# USB_ETH_Sch.net
KiCad netlist of a schematic drawn in Altium Designer
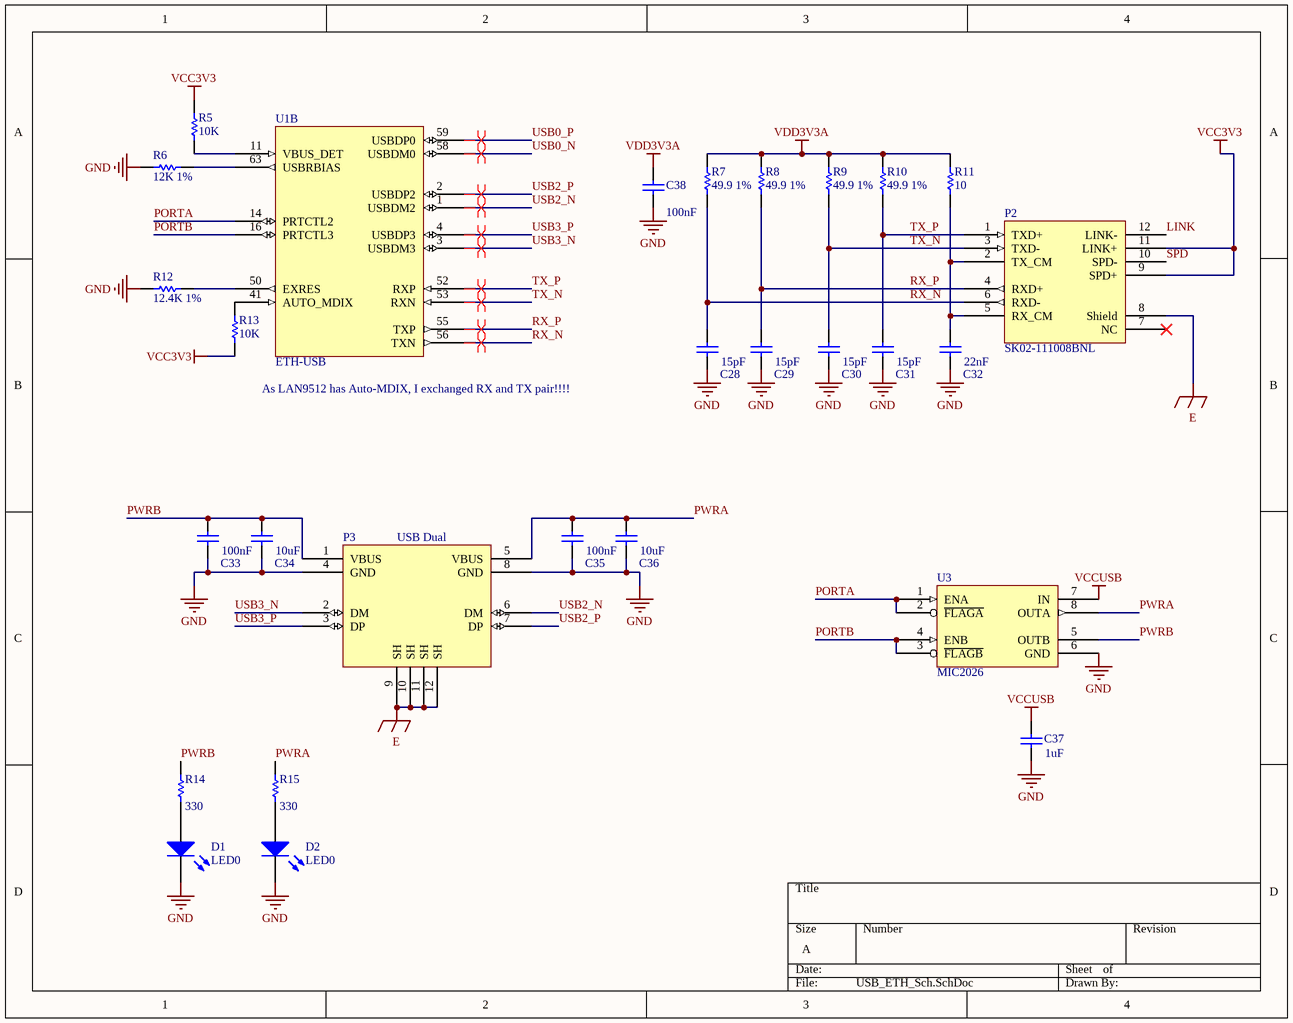
[diagram p0: USB_ETH_Sch.SchDoc]

(export (version "E")
  (design (tool "Eeschema 10.0.6"))
  (components
    (comp (ref "C28")
      (value "15pF")
      (footprint "C0805")
      (description "Capacitor")
      (fields (field (name "Comment") "Cap") (field (name "PUBLISHER") "Altium Limited"))
      (libsource (lib "Miscellaneous Devices") (part "Cap"))
    )
    (comp (ref "C29")
      (value "15pF")
      (footprint "C0805")
      (description "Capacitor")
      (fields (field (name "Comment") "Cap") (field (name "PUBLISHER") "Altium Limited"))
      (libsource (lib "Miscellaneous Devices") (part "Cap"))
    )
    (comp (ref "C30")
      (value "15pF")
      (footprint "C0805")
      (description "Capacitor")
      (fields (field (name "Comment") "Cap") (field (name "PUBLISHER") "Altium Limited"))
      (libsource (lib "Miscellaneous Devices") (part "Cap"))
    )
    (comp (ref "C31")
      (value "15pF")
      (footprint "C0805")
      (description "Capacitor")
      (fields (field (name "Comment") "Cap") (field (name "PUBLISHER") "Altium Limited"))
      (libsource (lib "Miscellaneous Devices") (part "Cap"))
    )
    (comp (ref "C32")
      (value "22nF")
      (footprint "C0805")
      (description "Capacitor")
      (fields (field (name "Comment") "Cap") (field (name "PUBLISHER") "Altium Limited"))
      (libsource (lib "Miscellaneous Devices") (part "Cap"))
    )
    (comp (ref "C33")
      (value "100nF")
      (footprint "C0805")
      (description "Capacitor")
      (fields (field (name "Comment") "Cap") (field (name "PUBLISHER") "Altium Limited"))
      (libsource (lib "Miscellaneous Devices") (part "Cap"))
    )
    (comp (ref "C34")
      (value "10uF")
      (footprint "C0805")
      (description "Capacitor")
      (fields (field (name "Comment") "Cap") (field (name "PUBLISHER") "Altium Limited"))
      (libsource (lib "Miscellaneous Devices") (part "Cap"))
    )
    (comp (ref "C35")
      (value "100nF")
      (footprint "C0805")
      (description "Capacitor")
      (fields (field (name "Comment") "Cap") (field (name "PUBLISHER") "Altium Limited"))
      (libsource (lib "Miscellaneous Devices") (part "Cap"))
    )
    (comp (ref "C36")
      (value "10uF")
      (footprint "C0805")
      (description "Capacitor")
      (fields (field (name "Comment") "Cap") (field (name "PUBLISHER") "Altium Limited"))
      (libsource (lib "Miscellaneous Devices") (part "Cap"))
    )
    (comp (ref "C37")
      (value "1uF")
      (footprint "C0805")
      (description "Capacitor")
      (fields (field (name "Comment") "Cap") (field (name "PUBLISHER") "Altium Limited"))
      (libsource (lib "Miscellaneous Devices") (part "Cap"))
    )
    (comp (ref "C38")
      (value "100nF")
      (footprint "C0805")
      (description "Capacitor")
      (fields (field (name "Comment") "Cap") (field (name "PUBLISHER") "Altium Limited"))
      (libsource (lib "Miscellaneous Devices") (part "Cap"))
    )
    (comp (ref "D1")
      (value "LED0")
      (footprint "SMD_LED_1206")
      (description "Typical INFRARED GaAs LED")
      (fields (field (name "PUBLISHER") "Altium Limited"))
      (libsource (lib "Miscellaneous Devices") (part "LED0"))
    )
    (comp (ref "D2")
      (value "LED0")
      (footprint "SMD_LED_1206")
      (description "Typical INFRARED GaAs LED")
      (fields (field (name "PUBLISHER") "Altium Limited"))
      (libsource (lib "Miscellaneous Devices") (part "LED0"))
    )
    (comp (ref "P2")
      (value "SK02-111008BNL")
      (footprint "RJ45+MAG")
      (description "Ethernet")
      (libsource (lib "Conn_Schlib") (part "SK02-111008BNL"))
    )
    (comp (ref "P3")
      (value "USB Dual")
      (footprint "USB_Duble")
      (libsource (lib "Connector_IntLib") (part "USB_Double_Female"))
    )
    (comp (ref "R5")
      (value "10K")
      (footprint "c0805")
      (description "Resistor")
      (fields (field (name "Comment") "Res1") (field (name "PUBLISHER") "Altium Limited"))
      (libsource (lib "Miscellaneous Devices") (part "Res1"))
    )
    (comp (ref "R6")
      (value "12K 1%")
      (footprint "c0805")
      (description "Resistor")
      (fields (field (name "Comment") "Res1") (field (name "PUBLISHER") "Altium Limited"))
      (libsource (lib "Miscellaneous Devices") (part "Res1"))
    )
    (comp (ref "R7")
      (value "49.9 1%")
      (footprint "c0805")
      (description "Resistor")
      (fields (field (name "Comment") "Res1") (field (name "PUBLISHER") "Altium Limited"))
      (libsource (lib "Miscellaneous Devices") (part "Res1"))
    )
    (comp (ref "R8")
      (value "49.9 1%")
      (footprint "c0805")
      (description "Resistor")
      (fields (field (name "Comment") "Res1") (field (name "PUBLISHER") "Altium Limited"))
      (libsource (lib "Miscellaneous Devices") (part "Res1"))
    )
    (comp (ref "R9")
      (value "49.9 1%")
      (footprint "c0805")
      (description "Resistor")
      (fields (field (name "Comment") "Res1") (field (name "PUBLISHER") "Altium Limited"))
      (libsource (lib "Miscellaneous Devices") (part "Res1"))
    )
    (comp (ref "R10")
      (value "49.9 1%")
      (footprint "c0805")
      (description "Resistor")
      (fields (field (name "Comment") "Res1") (field (name "PUBLISHER") "Altium Limited"))
      (libsource (lib "Miscellaneous Devices") (part "Res1"))
    )
    (comp (ref "R11")
      (value "10")
      (footprint "c0805")
      (description "Resistor")
      (fields (field (name "Comment") "Res1") (field (name "PUBLISHER") "Altium Limited"))
      (libsource (lib "Miscellaneous Devices") (part "Res1"))
    )
    (comp (ref "R12")
      (value "12.4K 1%")
      (footprint "c0805")
      (description "Resistor")
      (fields (field (name "Comment") "Res1") (field (name "PUBLISHER") "Altium Limited"))
      (libsource (lib "Miscellaneous Devices") (part "Res1"))
    )
    (comp (ref "R13")
      (value "10K")
      (footprint "c0805")
      (description "Resistor")
      (fields (field (name "Comment") "Res1") (field (name "PUBLISHER") "Altium Limited"))
      (libsource (lib "Miscellaneous Devices") (part "Res1"))
    )
    (comp (ref "R14")
      (value "330")
      (footprint "C1206")
      (description "Resistor")
      (fields (field (name "Comment") "Res1") (field (name "PUBLISHER") "Altium Limited"))
      (libsource (lib "Miscellaneous Devices") (part "Res1"))
    )
    (comp (ref "R15")
      (value "330")
      (footprint "C1206")
      (description "Resistor")
      (fields (field (name "Comment") "Res1") (field (name "PUBLISHER") "Altium Limited"))
      (libsource (lib "Miscellaneous Devices") (part "Res1"))
    )
    (comp (ref "U1")
      (value "ETH-USB")
      (footprint "QFN64")
      (description "USB Hub to LAN connevtor")
      (libsource (lib "Connector_IntLib") (part "LAN9512"))
    )
    (comp (ref "U3")
      (value "MIC2026")
      (footprint "SSOP8")
      (libsource (lib "Connector_IntLib") (part "MIC2026"))
    )
  )
  (nets
    (net (code "1") (name "/LINK") (class "Default")
      (node (ref "P2") (pin "12") (pinfunction "LINK-_12") (pintype "power_in"))
    )
    (net (code "2") (name "/PORTA") (class "Default")
      (node (ref "U1") (pin "14") (pinfunction "PRTCTL2_14") (pintype "bidirectional"))
      (node (ref "U3") (pin "1") (pinfunction "ENA_1") (pintype "input"))
      (node (ref "U3") (pin "2") (pinfunction "~{FLAGA}_2") (pintype "power_in"))
    )
    (net (code "3") (name "/PORTB") (class "Default")
      (node (ref "U1") (pin "16") (pinfunction "PRTCTL3_16") (pintype "bidirectional"))
      (node (ref "U3") (pin "3") (pinfunction "~{FLAGB}_3") (pintype "passive"))
      (node (ref "U3") (pin "4") (pinfunction "ENB_4") (pintype "input"))
    )
    (net (code "4") (name "/PWRA") (class "Default")
      (node (ref "C35") (pin "2") (pinfunction "2_2") (pintype "passive"))
      (node (ref "C36") (pin "2") (pinfunction "2_2") (pintype "passive"))
      (node (ref "P3") (pin "5") (pinfunction "VBUS_5") (pintype "power_in"))
      (node (ref "R15") (pin "2") (pinfunction "2_2") (pintype "passive"))
      (node (ref "U3") (pin "8") (pinfunction "OUTA_8") (pintype "output"))
    )
    (net (code "5") (name "/PWRB") (class "Default")
      (node (ref "C33") (pin "2") (pinfunction "2_2") (pintype "passive"))
      (node (ref "C34") (pin "2") (pinfunction "2_2") (pintype "passive"))
      (node (ref "P3") (pin "1") (pinfunction "VBUS_1") (pintype "power_in"))
      (node (ref "R14") (pin "2") (pinfunction "2_2") (pintype "passive"))
      (node (ref "U3") (pin "5") (pinfunction "OUTB_5") (pintype "power_in"))
    )
    (net (code "6") (name "/RX_N") (class "Default")
      (node (ref "C28") (pin "2") (pinfunction "2_2") (pintype "passive"))
      (node (ref "P2") (pin "6") (pinfunction "RXD-_6") (pintype "output"))
      (node (ref "R7") (pin "1") (pinfunction "1_1") (pintype "passive"))
      (node (ref "U1") (pin "56") (pinfunction "TXN_56") (pintype "output"))
    )
    (net (code "7") (name "/RX_P") (class "Default")
      (node (ref "C29") (pin "2") (pinfunction "2_2") (pintype "passive"))
      (node (ref "P2") (pin "4") (pinfunction "RXD+_4") (pintype "output"))
      (node (ref "R8") (pin "1") (pinfunction "1_1") (pintype "passive"))
      (node (ref "U1") (pin "55") (pinfunction "TXP_55") (pintype "output"))
    )
    (net (code "8") (name "/SPD") (class "Default")
      (node (ref "P2") (pin "10") (pinfunction "SPD-_10") (pintype "power_in"))
    )
    (net (code "9") (name "/TX_N") (class "Default")
      (node (ref "C30") (pin "2") (pinfunction "2_2") (pintype "passive"))
      (node (ref "P2") (pin "3") (pinfunction "TXD-_3") (pintype "input"))
      (node (ref "R9") (pin "1") (pinfunction "1_1") (pintype "passive"))
      (node (ref "U1") (pin "53") (pinfunction "RXN_53") (pintype "input"))
    )
    (net (code "10") (name "/TX_P") (class "Default")
      (node (ref "C31") (pin "2") (pinfunction "2_2") (pintype "passive"))
      (node (ref "P2") (pin "1") (pinfunction "TXD+_1") (pintype "input"))
      (node (ref "R10") (pin "1") (pinfunction "1_1") (pintype "passive"))
      (node (ref "U1") (pin "52") (pinfunction "RXP_52") (pintype "input"))
    )
    (net (code "11") (name "/USB0_N") (class "Default")
      (node (ref "U1") (pin "58") (pinfunction "USBDM0_58") (pintype "bidirectional"))
    )
    (net (code "12") (name "/USB0_P") (class "Default")
      (node (ref "U1") (pin "59") (pinfunction "USBDP0_59") (pintype "bidirectional"))
    )
    (net (code "13") (name "/USB2_N") (class "Default")
      (node (ref "P3") (pin "6") (pinfunction "DM_6") (pintype "bidirectional"))
      (node (ref "U1") (pin "1") (pinfunction "USBDM2_1") (pintype "bidirectional"))
    )
    (net (code "14") (name "/USB2_P") (class "Default")
      (node (ref "P3") (pin "7") (pinfunction "DP_7") (pintype "bidirectional"))
      (node (ref "U1") (pin "2") (pinfunction "USBDP2_2") (pintype "bidirectional"))
    )
    (net (code "15") (name "/USB3_N") (class "Default")
      (node (ref "P3") (pin "2") (pinfunction "DM_2") (pintype "bidirectional"))
      (node (ref "U1") (pin "3") (pinfunction "USBDM3_3") (pintype "bidirectional"))
    )
    (net (code "16") (name "/USB3_P") (class "Default")
      (node (ref "P3") (pin "3") (pinfunction "DP_3") (pintype "bidirectional"))
      (node (ref "U1") (pin "4") (pinfunction "USBDP3_4") (pintype "bidirectional"))
    )
    (net (code "17") (name "E") (class "Default")
      (node (ref "P2") (pin "8") (pinfunction "Shield_8") (pintype "passive"))
      (node (ref "P3") (pin "10") (pinfunction "SH_10") (pintype "passive"))
      (node (ref "P3") (pin "11") (pinfunction "SH_11") (pintype "passive"))
      (node (ref "P3") (pin "12") (pinfunction "SH_12") (pintype "passive"))
      (node (ref "P3") (pin "9") (pinfunction "SH_9") (pintype "passive"))
    )
    (net (code "18") (name "GND") (class "Default")
      (node (ref "C28") (pin "1") (pinfunction "1_1") (pintype "passive"))
      (node (ref "C29") (pin "1") (pinfunction "1_1") (pintype "passive"))
      (node (ref "C30") (pin "1") (pinfunction "1_1") (pintype "passive"))
      (node (ref "C31") (pin "1") (pinfunction "1_1") (pintype "passive"))
      (node (ref "C32") (pin "1") (pinfunction "1_1") (pintype "passive"))
      (node (ref "C33") (pin "1") (pinfunction "1_1") (pintype "passive"))
      (node (ref "C34") (pin "1") (pinfunction "1_1") (pintype "passive"))
      (node (ref "C35") (pin "1") (pinfunction "1_1") (pintype "passive"))
      (node (ref "C36") (pin "1") (pinfunction "1_1") (pintype "passive"))
      (node (ref "C37") (pin "1") (pinfunction "1_1") (pintype "passive"))
      (node (ref "C38") (pin "1") (pinfunction "1_1") (pintype "passive"))
      (node (ref "D1") (pin "2") (pinfunction "K_2") (pintype "passive"))
      (node (ref "D2") (pin "2") (pinfunction "K_2") (pintype "passive"))
      (node (ref "P3") (pin "4") (pinfunction "GND_4") (pintype "power_in"))
      (node (ref "P3") (pin "8") (pinfunction "GND_8") (pintype "power_in"))
      (node (ref "R12") (pin "1") (pinfunction "1_1") (pintype "passive"))
      (node (ref "R6") (pin "1") (pinfunction "1_1") (pintype "passive"))
      (node (ref "U3") (pin "6") (pinfunction "GND_6") (pintype "power_in"))
    )
    (net (code "19") (name "Net-(D1-A)") (class "Default")
      (node (ref "D1") (pin "1") (pinfunction "A_1") (pintype "passive"))
      (node (ref "R14") (pin "1") (pinfunction "1_1") (pintype "passive"))
    )
    (net (code "20") (name "Net-(D2-A)") (class "Default")
      (node (ref "D2") (pin "1") (pinfunction "A_1") (pintype "passive"))
      (node (ref "R15") (pin "1") (pinfunction "1_1") (pintype "passive"))
    )
    (net (code "21") (name "Net-(P2-RX_CM)") (class "Default")
      (node (ref "C32") (pin "2") (pinfunction "2_2") (pintype "passive"))
      (node (ref "P2") (pin "2") (pinfunction "TX_CM_2") (pintype "power_in"))
      (node (ref "P2") (pin "5") (pinfunction "RX_CM_5") (pintype "power_in"))
      (node (ref "R11") (pin "1") (pinfunction "1_1") (pintype "passive"))
    )
    (net (code "22") (name "Net-(U1B-AUTO_MDIX)") (class "Default")
      (node (ref "R13") (pin "2") (pinfunction "2_2") (pintype "passive"))
      (node (ref "U1") (pin "41") (pinfunction "AUTO_MDIX_41") (pintype "input"))
    )
    (net (code "23") (name "Net-(U1B-EXRES)") (class "Default")
      (node (ref "R12") (pin "2") (pinfunction "2_2") (pintype "passive"))
      (node (ref "U1") (pin "50") (pinfunction "EXRES_50") (pintype "output"))
    )
    (net (code "24") (name "Net-(U1B-USBRBIAS)") (class "Default")
      (node (ref "R6") (pin "2") (pinfunction "2_2") (pintype "passive"))
      (node (ref "U1") (pin "63") (pinfunction "USBRBIAS_63") (pintype "output"))
    )
    (net (code "25") (name "Net-(U1B-VBUS_DET)") (class "Default")
      (node (ref "R5") (pin "2") (pinfunction "2_2") (pintype "passive"))
      (node (ref "U1") (pin "11") (pinfunction "VBUS_DET_11") (pintype "input"))
    )
    (net (code "26") (name "VCC3V3") (class "Default")
      (node (ref "P2") (pin "11") (pinfunction "LINK+_11") (pintype "power_in"))
      (node (ref "P2") (pin "9") (pinfunction "SPD+_9") (pintype "power_in"))
      (node (ref "R13") (pin "1") (pinfunction "1_1") (pintype "passive"))
      (node (ref "R5") (pin "1") (pinfunction "1_1") (pintype "passive"))
    )
    (net (code "27") (name "VCCUSB") (class "Default")
      (node (ref "C37") (pin "2") (pinfunction "2_2") (pintype "passive"))
      (node (ref "U3") (pin "7") (pinfunction "IN_7") (pintype "power_in"))
    )
    (net (code "28") (name "VDD3V3A") (class "Default")
      (node (ref "C38") (pin "2") (pinfunction "2_2") (pintype "passive"))
      (node (ref "R10") (pin "2") (pinfunction "2_2") (pintype "passive"))
      (node (ref "R11") (pin "2") (pinfunction "2_2") (pintype "passive"))
      (node (ref "R7") (pin "2") (pinfunction "2_2") (pintype "passive"))
      (node (ref "R8") (pin "2") (pinfunction "2_2") (pintype "passive"))
      (node (ref "R9") (pin "2") (pinfunction "2_2") (pintype "passive"))
    )
    (net (code "29") (name "unconnected-(P2-NC-Pad7)") (class "Default")
      (node (ref "P2") (pin "7") (pinfunction "NC_7") (pintype "passive+no_connect"))
    )
  )
)
